# fat2.net
KiCad netlist of a schematic drawn in EAGLE
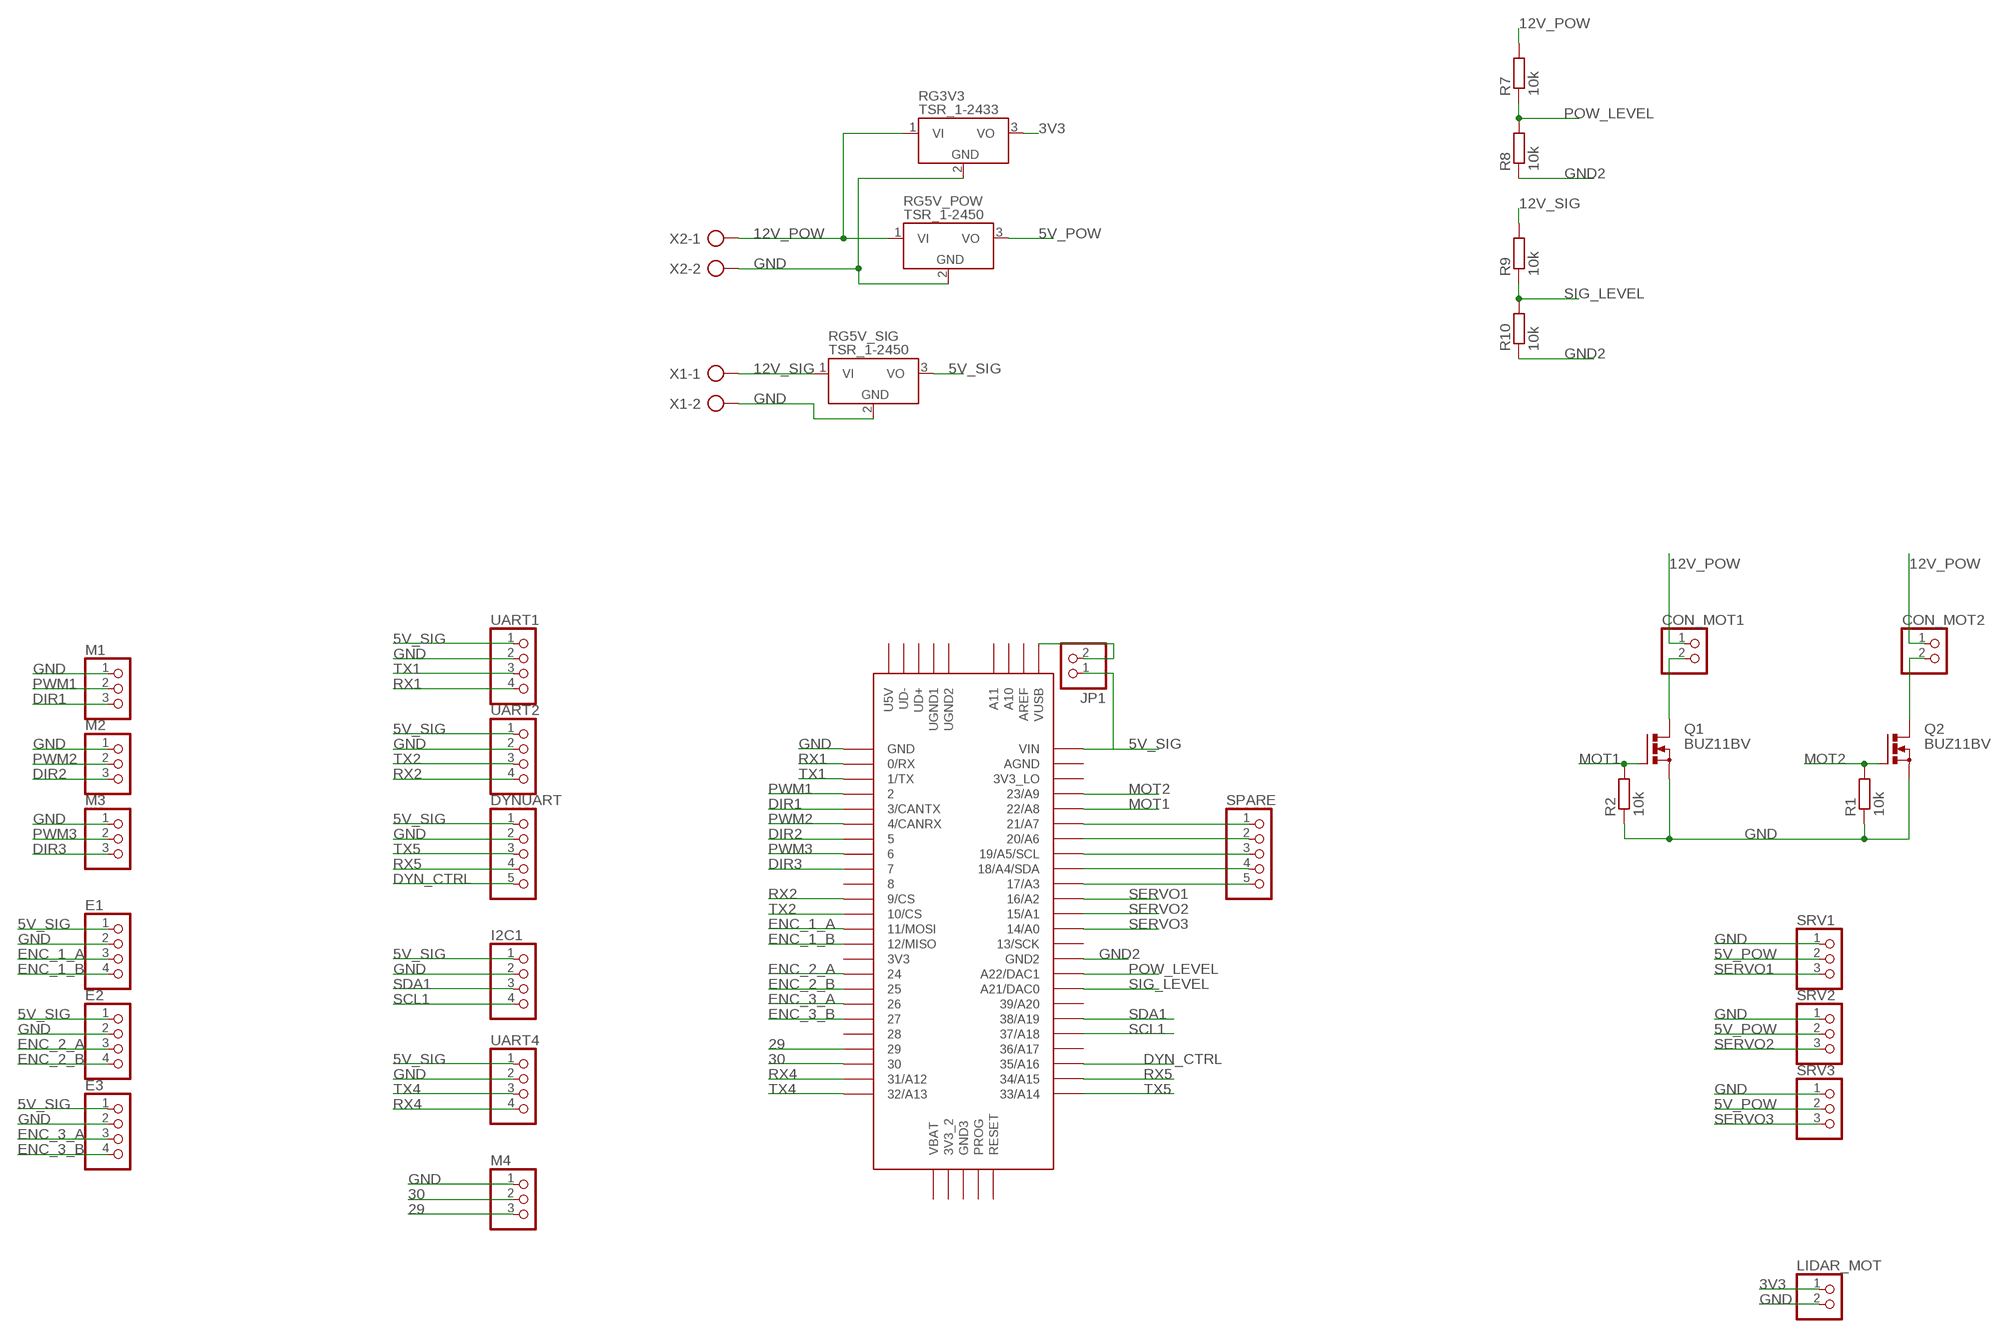
[diagram p0: schematic, sheet 1]

(export (version "E")
  (design (tool "Eeschema 10.0.6"))
  (components
    (comp (ref "CON_MOT1")
      (value "PINHD-1X2")
      (footprint "eagle-import:1X02")
      (libsource (lib "eagle-import") (part "PINHD-1X2"))
    )
    (comp (ref "CON_MOT2")
      (value "PINHD-1X2")
      (footprint "eagle-import:1X02")
      (libsource (lib "eagle-import") (part "PINHD-1X2"))
    )
    (comp (ref "DYNUART")
      (value "PINHD-1X5")
      (footprint "eagle-import:1X05")
      (libsource (lib "eagle-import") (part "PINHD-1X5"))
    )
    (comp (ref "E1")
      (value "PINHD-1X4")
      (footprint "eagle-import:1X04")
      (libsource (lib "eagle-import") (part "PINHD-1X4"))
    )
    (comp (ref "E2")
      (value "PINHD-1X4")
      (footprint "eagle-import:1X04")
      (libsource (lib "eagle-import") (part "PINHD-1X4"))
    )
    (comp (ref "E3")
      (value "PINHD-1X4")
      (footprint "eagle-import:1X04")
      (libsource (lib "eagle-import") (part "PINHD-1X4"))
    )
    (comp (ref "I2C1")
      (value "PINHD-1X4")
      (footprint "eagle-import:1X04")
      (libsource (lib "eagle-import") (part "PINHD-1X4"))
    )
    (comp (ref "JP1")
      (value "PINHD-1X2/90")
      (footprint "eagle-import:1X02_90")
      (libsource (lib "eagle-import") (part "PINHD-1X2/90"))
    )
    (comp (ref "LIDAR_MOT")
      (value "PINHD-1X2")
      (footprint "eagle-import:1X02")
      (libsource (lib "eagle-import") (part "PINHD-1X2"))
    )
    (comp (ref "M1")
      (value "PINHD-1X3")
      (footprint "eagle-import:1X03")
      (libsource (lib "eagle-import") (part "PINHD-1X3"))
    )
    (comp (ref "M2")
      (value "PINHD-1X3")
      (footprint "eagle-import:1X03")
      (libsource (lib "eagle-import") (part "PINHD-1X3"))
    )
    (comp (ref "M3")
      (value "PINHD-1X3")
      (footprint "eagle-import:1X03")
      (libsource (lib "eagle-import") (part "PINHD-1X3"))
    )
    (comp (ref "M4")
      (value "PINHD-1X3")
      (footprint "eagle-import:1X03")
      (libsource (lib "eagle-import") (part "PINHD-1X3"))
    )
    (comp (ref "Q1")
      (value "BUZ11BV")
      (footprint "eagle-import:TO220BV")
      (libsource (lib "eagle-import") (part "BUZ11BV"))
    )
    (comp (ref "Q2")
      (value "BUZ11BV")
      (footprint "eagle-import:TO220BV")
      (libsource (lib "eagle-import") (part "BUZ11BV"))
    )
    (comp (ref "R1")
      (value "10k")
      (footprint "eagle-import:0204_7")
      (libsource (lib "eagle-import") (part "R-EU_0204/7"))
    )
    (comp (ref "R2")
      (value "10k")
      (footprint "eagle-import:0204_7")
      (libsource (lib "eagle-import") (part "R-EU_0204/7"))
    )
    (comp (ref "R7")
      (value "10k")
      (footprint "eagle-import:0204_7")
      (libsource (lib "eagle-import") (part "R-EU_0204/7"))
    )
    (comp (ref "R8")
      (value "10k")
      (footprint "eagle-import:0204_7")
      (libsource (lib "eagle-import") (part "R-EU_0204/7"))
    )
    (comp (ref "R9")
      (value "10k")
      (footprint "eagle-import:0204_7")
      (libsource (lib "eagle-import") (part "R-EU_0204/7"))
    )
    (comp (ref "R10")
      (value "10k")
      (footprint "eagle-import:0204_7")
      (libsource (lib "eagle-import") (part "R-EU_0204/7"))
    )
    (comp (ref "RG3V3")
      (value "TSR_1-2433")
      (footprint "eagle-import:TSR-1")
      (libsource (lib "eagle-import") (part "TSR_1-2433"))
    )
    (comp (ref "RG5V_POW")
      (value "TSR_1-2450")
      (footprint "eagle-import:TSR-1")
      (libsource (lib "eagle-import") (part "TSR_1-2450"))
    )
    (comp (ref "RG5V_SIG")
      (value "TSR_1-2450")
      (footprint "eagle-import:TSR-1")
      (libsource (lib "eagle-import") (part "TSR_1-2450"))
    )
    (comp (ref "SPARE")
      (value "PINHD-1X5")
      (footprint "eagle-import:1X05")
      (libsource (lib "eagle-import") (part "PINHD-1X5"))
    )
    (comp (ref "SRV1")
      (value "PINHD-1X3")
      (footprint "eagle-import:1X03")
      (libsource (lib "eagle-import") (part "PINHD-1X3"))
    )
    (comp (ref "SRV2")
      (value "PINHD-1X3")
      (footprint "eagle-import:1X03")
      (libsource (lib "eagle-import") (part "PINHD-1X3"))
    )
    (comp (ref "SRV3")
      (value "PINHD-1X3")
      (footprint "eagle-import:1X03")
      (libsource (lib "eagle-import") (part "PINHD-1X3"))
    )
    (comp (ref "U$1")
      (value "TEENSY_3.5/3.6")
      (footprint "eagle-import:TEENSY_3.5_3.6")
      (libsource (lib "eagle-import") (part "TEENSY_3.5/3.6"))
    )
    (comp (ref "UART1")
      (value "PINHD-1X4")
      (footprint "eagle-import:1X04")
      (libsource (lib "eagle-import") (part "PINHD-1X4"))
    )
    (comp (ref "UART2")
      (value "PINHD-1X4")
      (footprint "eagle-import:1X04")
      (libsource (lib "eagle-import") (part "PINHD-1X4"))
    )
    (comp (ref "UART4")
      (value "PINHD-1X4")
      (footprint "eagle-import:1X04")
      (libsource (lib "eagle-import") (part "PINHD-1X4"))
    )
    (comp (ref "X1")
      (value "AK300/2")
      (footprint "eagle-import:AK300_2")
      (libsource (lib "eagle-import") (part "AK300/2"))
    )
    (comp (ref "X2")
      (value "AK300/2")
      (footprint "eagle-import:AK300_2")
      (libsource (lib "eagle-import") (part "AK300/2"))
    )
  )
  (nets
    (net (code "1") (name "/3V3") (class "Default")
      (node (ref "LIDAR_MOT") (pin "1") (pinfunction "1_1") (pintype "passive"))
      (node (ref "RG3V3") (pin "3") (pinfunction "VO_3") (pintype "power_in"))
    )
    (net (code "2") (name "/5V_POW") (class "Default")
      (node (ref "RG5V_POW") (pin "3") (pinfunction "VO_3") (pintype "power_in"))
      (node (ref "SRV1") (pin "2") (pinfunction "2_2") (pintype "passive"))
      (node (ref "SRV2") (pin "2") (pinfunction "2_2") (pintype "passive"))
      (node (ref "SRV3") (pin "2") (pinfunction "2_2") (pintype "passive"))
    )
    (net (code "3") (name "/5V_SIG") (class "Default")
      (node (ref "DYNUART") (pin "1") (pinfunction "1_1") (pintype "passive"))
      (node (ref "E1") (pin "1") (pinfunction "1_1") (pintype "passive"))
      (node (ref "E2") (pin "1") (pinfunction "1_1") (pintype "passive"))
      (node (ref "E3") (pin "1") (pinfunction "1_1") (pintype "passive"))
      (node (ref "I2C1") (pin "1") (pinfunction "1_1") (pintype "passive"))
      (node (ref "JP1") (pin "1") (pinfunction "1_1") (pintype "passive"))
      (node (ref "RG5V_SIG") (pin "3") (pinfunction "VO_3") (pintype "power_in"))
      (node (ref "U$1") (pin "VIN") (pinfunction "VIN_VIN") (pintype "bidirectional"))
      (node (ref "UART1") (pin "1") (pinfunction "1_1") (pintype "passive"))
      (node (ref "UART2") (pin "1") (pinfunction "1_1") (pintype "passive"))
      (node (ref "UART4") (pin "1") (pinfunction "1_1") (pintype "passive"))
    )
    (net (code "4") (name "/12V_POW") (class "Default")
      (node (ref "CON_MOT1") (pin "1") (pinfunction "1_1") (pintype "passive"))
      (node (ref "CON_MOT2") (pin "1") (pinfunction "1_1") (pintype "passive"))
      (node (ref "R7") (pin "2") (pinfunction "2_2") (pintype "passive"))
      (node (ref "RG3V3") (pin "1") (pinfunction "VI_1") (pintype "power_in"))
      (node (ref "RG5V_POW") (pin "1") (pinfunction "VI_1") (pintype "power_in"))
      (node (ref "X2") (pin "1") (pinfunction "KL_1") (pintype "passive"))
    )
    (net (code "5") (name "/12V_SIG") (class "Default")
      (node (ref "R9") (pin "2") (pinfunction "2_2") (pintype "passive"))
      (node (ref "RG5V_SIG") (pin "1") (pinfunction "VI_1") (pintype "power_in"))
      (node (ref "X1") (pin "1") (pinfunction "KL_1") (pintype "passive"))
    )
    (net (code "6") (name "/29") (class "Default")
      (node (ref "M4") (pin "3") (pinfunction "3_3") (pintype "passive"))
      (node (ref "U$1") (pin "29") (pinfunction "29_29") (pintype "bidirectional"))
    )
    (net (code "7") (name "/30") (class "Default")
      (node (ref "M4") (pin "2") (pinfunction "2_2") (pintype "passive"))
      (node (ref "U$1") (pin "30") (pinfunction "30_30") (pintype "bidirectional"))
    )
    (net (code "8") (name "/DIR1") (class "Default")
      (node (ref "M1") (pin "3") (pinfunction "3_3") (pintype "passive"))
      (node (ref "U$1") (pin "3/CANTX") (pinfunction "3/CANTX_3/CANTX") (pintype "bidirectional"))
    )
    (net (code "9") (name "/DIR2") (class "Default")
      (node (ref "M2") (pin "3") (pinfunction "3_3") (pintype "passive"))
      (node (ref "U$1") (pin "5") (pinfunction "5_5") (pintype "bidirectional"))
    )
    (net (code "10") (name "/DIR3") (class "Default")
      (node (ref "M3") (pin "3") (pinfunction "3_3") (pintype "passive"))
      (node (ref "U$1") (pin "7") (pinfunction "7_7") (pintype "bidirectional"))
    )
    (net (code "11") (name "/DYN_CTRL") (class "Default")
      (node (ref "DYNUART") (pin "5") (pinfunction "5_5") (pintype "passive"))
      (node (ref "U$1") (pin "35/A16") (pinfunction "35/A16_35/A16") (pintype "bidirectional"))
    )
    (net (code "12") (name "/ENC_1_A") (class "Default")
      (node (ref "E1") (pin "3") (pinfunction "3_3") (pintype "passive"))
      (node (ref "U$1") (pin "11/MOSI") (pinfunction "11/MOSI_11/MOSI") (pintype "bidirectional"))
    )
    (net (code "13") (name "/ENC_1_B") (class "Default")
      (node (ref "E1") (pin "4") (pinfunction "4_4") (pintype "passive"))
      (node (ref "U$1") (pin "12/MISO") (pinfunction "12/MISO_12/MISO") (pintype "bidirectional"))
    )
    (net (code "14") (name "/ENC_2_A") (class "Default")
      (node (ref "E2") (pin "3") (pinfunction "3_3") (pintype "passive"))
      (node (ref "U$1") (pin "24") (pinfunction "24_24") (pintype "bidirectional"))
    )
    (net (code "15") (name "/ENC_2_B") (class "Default")
      (node (ref "E2") (pin "4") (pinfunction "4_4") (pintype "passive"))
      (node (ref "U$1") (pin "25") (pinfunction "25_25") (pintype "bidirectional"))
    )
    (net (code "16") (name "/ENC_3_A") (class "Default")
      (node (ref "E3") (pin "3") (pinfunction "3_3") (pintype "passive"))
      (node (ref "U$1") (pin "26") (pinfunction "26_26") (pintype "bidirectional"))
    )
    (net (code "17") (name "/ENC_3_B") (class "Default")
      (node (ref "E3") (pin "4") (pinfunction "4_4") (pintype "passive"))
      (node (ref "U$1") (pin "27") (pinfunction "27_27") (pintype "bidirectional"))
    )
    (net (code "18") (name "/GND") (class "Default")
      (node (ref "DYNUART") (pin "2") (pinfunction "2_2") (pintype "passive"))
      (node (ref "E1") (pin "2") (pinfunction "2_2") (pintype "passive"))
      (node (ref "E2") (pin "2") (pinfunction "2_2") (pintype "passive"))
      (node (ref "E3") (pin "2") (pinfunction "2_2") (pintype "passive"))
      (node (ref "I2C1") (pin "2") (pinfunction "2_2") (pintype "passive"))
      (node (ref "LIDAR_MOT") (pin "2") (pinfunction "2_2") (pintype "passive"))
      (node (ref "M1") (pin "1") (pinfunction "1_1") (pintype "passive"))
      (node (ref "M2") (pin "1") (pinfunction "1_1") (pintype "passive"))
      (node (ref "M3") (pin "1") (pinfunction "1_1") (pintype "passive"))
      (node (ref "M4") (pin "1") (pinfunction "1_1") (pintype "passive"))
      (node (ref "Q1") (pin "S") (pinfunction "S_S") (pintype "passive"))
      (node (ref "Q2") (pin "S") (pinfunction "S_S") (pintype "passive"))
      (node (ref "R1") (pin "1") (pinfunction "1_1") (pintype "passive"))
      (node (ref "R2") (pin "1") (pinfunction "1_1") (pintype "passive"))
      (node (ref "RG3V3") (pin "2") (pinfunction "GND_2") (pintype "power_in"))
      (node (ref "RG5V_POW") (pin "2") (pinfunction "GND_2") (pintype "power_in"))
      (node (ref "RG5V_SIG") (pin "2") (pinfunction "GND_2") (pintype "power_in"))
      (node (ref "SRV1") (pin "1") (pinfunction "1_1") (pintype "passive"))
      (node (ref "SRV2") (pin "1") (pinfunction "1_1") (pintype "passive"))
      (node (ref "SRV3") (pin "1") (pinfunction "1_1") (pintype "passive"))
      (node (ref "U$1") (pin "GND") (pinfunction "GND_GND") (pintype "bidirectional"))
      (node (ref "UART1") (pin "2") (pinfunction "2_2") (pintype "passive"))
      (node (ref "UART2") (pin "2") (pinfunction "2_2") (pintype "passive"))
      (node (ref "UART4") (pin "2") (pinfunction "2_2") (pintype "passive"))
      (node (ref "X1") (pin "2") (pinfunction "KL_2") (pintype "passive"))
      (node (ref "X2") (pin "2") (pinfunction "KL_2") (pintype "passive"))
    )
    (net (code "19") (name "/GND2") (class "Default")
      (node (ref "R10") (pin "1") (pinfunction "1_1") (pintype "passive"))
      (node (ref "R8") (pin "1") (pinfunction "1_1") (pintype "passive"))
      (node (ref "U$1") (pin "GND2") (pinfunction "GND2_GND2") (pintype "bidirectional"))
    )
    (net (code "20") (name "/MOT1") (class "Default")
      (node (ref "Q1") (pin "G") (pinfunction "G_G") (pintype "passive"))
      (node (ref "R2") (pin "2") (pinfunction "2_2") (pintype "passive"))
      (node (ref "U$1") (pin "22/A8") (pinfunction "22/A8_22/A8") (pintype "bidirectional"))
    )
    (net (code "21") (name "/MOT2") (class "Default")
      (node (ref "Q2") (pin "G") (pinfunction "G_G") (pintype "passive"))
      (node (ref "R1") (pin "2") (pinfunction "2_2") (pintype "passive"))
      (node (ref "U$1") (pin "23/A9") (pinfunction "23/A9_23/A9") (pintype "bidirectional"))
    )
    (net (code "22") (name "/POW_LEVEL") (class "Default")
      (node (ref "R7") (pin "1") (pinfunction "1_1") (pintype "passive"))
      (node (ref "R8") (pin "2") (pinfunction "2_2") (pintype "passive"))
      (node (ref "U$1") (pin "A22/DAC1") (pinfunction "A22/DAC1_A22/DAC1") (pintype "bidirectional"))
    )
    (net (code "23") (name "/PWM1") (class "Default")
      (node (ref "M1") (pin "2") (pinfunction "2_2") (pintype "passive"))
      (node (ref "U$1") (pin "2") (pinfunction "2_2") (pintype "bidirectional"))
    )
    (net (code "24") (name "/PWM2") (class "Default")
      (node (ref "M2") (pin "2") (pinfunction "2_2") (pintype "passive"))
      (node (ref "U$1") (pin "4/CANRX") (pinfunction "4/CANRX_4/CANRX") (pintype "bidirectional"))
    )
    (net (code "25") (name "/PWM3") (class "Default")
      (node (ref "M3") (pin "2") (pinfunction "2_2") (pintype "passive"))
      (node (ref "U$1") (pin "6") (pinfunction "6_6") (pintype "bidirectional"))
    )
    (net (code "26") (name "/RX1") (class "Default")
      (node (ref "U$1") (pin "0/RX") (pinfunction "0/RX_0/RX") (pintype "bidirectional"))
      (node (ref "UART1") (pin "4") (pinfunction "4_4") (pintype "passive"))
    )
    (net (code "27") (name "/RX2") (class "Default")
      (node (ref "U$1") (pin "9/CS") (pinfunction "9/CS_9/CS") (pintype "bidirectional"))
      (node (ref "UART2") (pin "4") (pinfunction "4_4") (pintype "passive"))
    )
    (net (code "28") (name "/RX4") (class "Default")
      (node (ref "U$1") (pin "31/A12") (pinfunction "31/A12_31/A12") (pintype "bidirectional"))
      (node (ref "UART4") (pin "4") (pinfunction "4_4") (pintype "passive"))
    )
    (net (code "29") (name "/RX5") (class "Default")
      (node (ref "DYNUART") (pin "4") (pinfunction "4_4") (pintype "passive"))
      (node (ref "U$1") (pin "34/A15") (pinfunction "34/A15_34/A15") (pintype "bidirectional"))
    )
    (net (code "30") (name "/SCL1") (class "Default")
      (node (ref "I2C1") (pin "4") (pinfunction "4_4") (pintype "passive"))
      (node (ref "U$1") (pin "37/A18") (pinfunction "37/A18_37/A18") (pintype "bidirectional"))
    )
    (net (code "31") (name "/SDA1") (class "Default")
      (node (ref "I2C1") (pin "3") (pinfunction "3_3") (pintype "passive"))
      (node (ref "U$1") (pin "38/A19") (pinfunction "38/A19_38/A19") (pintype "bidirectional"))
    )
    (net (code "32") (name "/SERVO1") (class "Default")
      (node (ref "SRV1") (pin "3") (pinfunction "3_3") (pintype "passive"))
      (node (ref "U$1") (pin "16/A2") (pinfunction "16/A2_16/A2") (pintype "bidirectional"))
    )
    (net (code "33") (name "/SERVO2") (class "Default")
      (node (ref "SRV2") (pin "3") (pinfunction "3_3") (pintype "passive"))
      (node (ref "U$1") (pin "15/A1") (pinfunction "15/A1_15/A1") (pintype "bidirectional"))
    )
    (net (code "34") (name "/SERVO3") (class "Default")
      (node (ref "SRV3") (pin "3") (pinfunction "3_3") (pintype "passive"))
      (node (ref "U$1") (pin "14/A0") (pinfunction "14/A0_14/A0") (pintype "bidirectional"))
    )
    (net (code "35") (name "/SIG_LEVEL") (class "Default")
      (node (ref "R10") (pin "2") (pinfunction "2_2") (pintype "passive"))
      (node (ref "R9") (pin "1") (pinfunction "1_1") (pintype "passive"))
      (node (ref "U$1") (pin "21/DAC0") (pinfunction "A21/DAC0_21/DAC0") (pintype "bidirectional"))
    )
    (net (code "36") (name "/TX1") (class "Default")
      (node (ref "U$1") (pin "1/TX") (pinfunction "1/TX_1/TX") (pintype "bidirectional"))
      (node (ref "UART1") (pin "3") (pinfunction "3_3") (pintype "passive"))
    )
    (net (code "37") (name "/TX2") (class "Default")
      (node (ref "U$1") (pin "10/CS") (pinfunction "10/CS_10/CS") (pintype "bidirectional"))
      (node (ref "UART2") (pin "3") (pinfunction "3_3") (pintype "passive"))
    )
    (net (code "38") (name "/TX4") (class "Default")
      (node (ref "U$1") (pin "32/A13") (pinfunction "32/A13_32/A13") (pintype "bidirectional"))
      (node (ref "UART4") (pin "3") (pinfunction "3_3") (pintype "passive"))
    )
    (net (code "39") (name "/TX5") (class "Default")
      (node (ref "DYNUART") (pin "3") (pinfunction "3_3") (pintype "passive"))
      (node (ref "U$1") (pin "33/A14") (pinfunction "33/A14_33/A14") (pintype "bidirectional"))
    )
    (net (code "40") (name "Net-(CON_MOT1-Pad2)") (class "Default")
      (node (ref "CON_MOT1") (pin "2") (pinfunction "2_2") (pintype "passive"))
      (node (ref "Q1") (pin "D") (pinfunction "D_D") (pintype "passive"))
    )
    (net (code "41") (name "Net-(CON_MOT2-Pad2)") (class "Default")
      (node (ref "CON_MOT2") (pin "2") (pinfunction "2_2") (pintype "passive"))
      (node (ref "Q2") (pin "D") (pinfunction "D_D") (pintype "passive"))
    )
    (net (code "42") (name "Net-(JP1-Pad2)") (class "Default")
      (node (ref "JP1") (pin "2") (pinfunction "2_2") (pintype "passive"))
      (node (ref "U$1") (pin "VUSB") (pinfunction "VUSB_VUSB") (pintype "bidirectional"))
    )
    (net (code "43") (name "Net-(SPARE-Pad1)") (class "Default")
      (node (ref "SPARE") (pin "1") (pinfunction "1_1") (pintype "passive"))
      (node (ref "U$1") (pin "21/A7") (pinfunction "21/A7_21/A7") (pintype "bidirectional"))
    )
    (net (code "44") (name "Net-(SPARE-Pad2)") (class "Default")
      (node (ref "SPARE") (pin "2") (pinfunction "2_2") (pintype "passive"))
      (node (ref "U$1") (pin "20/A6") (pinfunction "20/A6_20/A6") (pintype "bidirectional"))
    )
    (net (code "45") (name "Net-(SPARE-Pad3)") (class "Default")
      (node (ref "SPARE") (pin "3") (pinfunction "3_3") (pintype "passive"))
      (node (ref "U$1") (pin "19/A5/SCL") (pinfunction "19/A5/SCL_19/A5/SCL") (pintype "bidirectional"))
    )
    (net (code "46") (name "Net-(SPARE-Pad4)") (class "Default")
      (node (ref "SPARE") (pin "4") (pinfunction "4_4") (pintype "passive"))
      (node (ref "U$1") (pin "18/A4/SDA") (pinfunction "18/A4/SDA_18/A4/SDA") (pintype "bidirectional"))
    )
    (net (code "47") (name "Net-(SPARE-Pad5)") (class "Default")
      (node (ref "SPARE") (pin "5") (pinfunction "5_5") (pintype "passive"))
      (node (ref "U$1") (pin "17/A3") (pinfunction "17/A3_17/A3") (pintype "bidirectional"))
    )
    (net (code "48") (name "unconnected-(U$1-Pad3V3)") (class "Default")
      (node (ref "U$1") (pin "3V3") (pinfunction "3V3_3V3") (pintype "bidirectional"))
    )
    (net (code "49") (name "unconnected-(U$1-Pad3V3_2)") (class "Default")
      (node (ref "U$1") (pin "3V3_2") (pinfunction "3V3_2_3V3_2") (pintype "bidirectional"))
    )
    (net (code "50") (name "unconnected-(U$1-Pad3V3_LO)") (class "Default")
      (node (ref "U$1") (pin "3V3_LO") (pinfunction "3V3_LO_3V3_LO") (pintype "bidirectional"))
    )
    (net (code "51") (name "unconnected-(U$1-Pad8)") (class "Default")
      (node (ref "U$1") (pin "8") (pinfunction "8_8") (pintype "bidirectional"))
    )
    (net (code "52") (name "unconnected-(U$1-Pad13{slash}SCK)") (class "Default")
      (node (ref "U$1") (pin "13/SCK") (pinfunction "13/SCK_13/SCK") (pintype "bidirectional"))
    )
    (net (code "53") (name "unconnected-(U$1-Pad28)") (class "Default")
      (node (ref "U$1") (pin "28") (pinfunction "28_28") (pintype "bidirectional"))
    )
    (net (code "54") (name "unconnected-(U$1-Pad36{slash}A17)") (class "Default")
      (node (ref "U$1") (pin "36/A17") (pinfunction "36/A17_36/A17") (pintype "bidirectional"))
    )
    (net (code "55") (name "unconnected-(U$1-Pad39{slash}A20)") (class "Default")
      (node (ref "U$1") (pin "39/A20") (pinfunction "39/A20_39/A20") (pintype "bidirectional"))
    )
    (net (code "56") (name "unconnected-(U$1-PadA10)") (class "Default")
      (node (ref "U$1") (pin "A10") (pinfunction "A10_A10") (pintype "bidirectional"))
    )
    (net (code "57") (name "unconnected-(U$1-PadA11)") (class "Default")
      (node (ref "U$1") (pin "A11") (pinfunction "A11_A11") (pintype "bidirectional"))
    )
    (net (code "58") (name "unconnected-(U$1-PadAGND)") (class "Default")
      (node (ref "U$1") (pin "AGND") (pinfunction "AGND_AGND") (pintype "bidirectional"))
    )
    (net (code "59") (name "unconnected-(U$1-PadAREF)") (class "Default")
      (node (ref "U$1") (pin "AREF") (pinfunction "AREF_AREF") (pintype "bidirectional"))
    )
    (net (code "60") (name "unconnected-(U$1-PadGND3)") (class "Default")
      (node (ref "U$1") (pin "GND3") (pinfunction "GND3_GND3") (pintype "bidirectional"))
    )
    (net (code "61") (name "unconnected-(U$1-PadPROG)") (class "Default")
      (node (ref "U$1") (pin "PROG") (pinfunction "PROG_PROG") (pintype "bidirectional"))
    )
    (net (code "62") (name "unconnected-(U$1-PadRESET)") (class "Default")
      (node (ref "U$1") (pin "RESET") (pinfunction "RESET_RESET") (pintype "bidirectional"))
    )
    (net (code "63") (name "unconnected-(U$1-PadU5V)") (class "Default")
      (node (ref "U$1") (pin "U5V") (pinfunction "U5V_U5V") (pintype "bidirectional"))
    )
    (net (code "64") (name "unconnected-(U$1-PadUD+)") (class "Default")
      (node (ref "U$1") (pin "UD+") (pinfunction "UD+_UD+") (pintype "bidirectional"))
    )
    (net (code "65") (name "unconnected-(U$1-PadUD-)") (class "Default")
      (node (ref "U$1") (pin "UD-") (pinfunction "UD-_UD-") (pintype "bidirectional"))
    )
    (net (code "66") (name "unconnected-(U$1-PadUGND1)") (class "Default")
      (node (ref "U$1") (pin "UGND1") (pinfunction "UGND1_UGND1") (pintype "bidirectional"))
    )
    (net (code "67") (name "unconnected-(U$1-PadUGND2)") (class "Default")
      (node (ref "U$1") (pin "UGND2") (pinfunction "UGND2_UGND2") (pintype "bidirectional"))
    )
    (net (code "68") (name "unconnected-(U$1-PadVBAT)") (class "Default")
      (node (ref "U$1") (pin "VBAT") (pinfunction "VBAT_VBAT") (pintype "bidirectional"))
    )
  )
)
